# pic24OLED.net
KiCad netlist of a schematic drawn in EAGLE
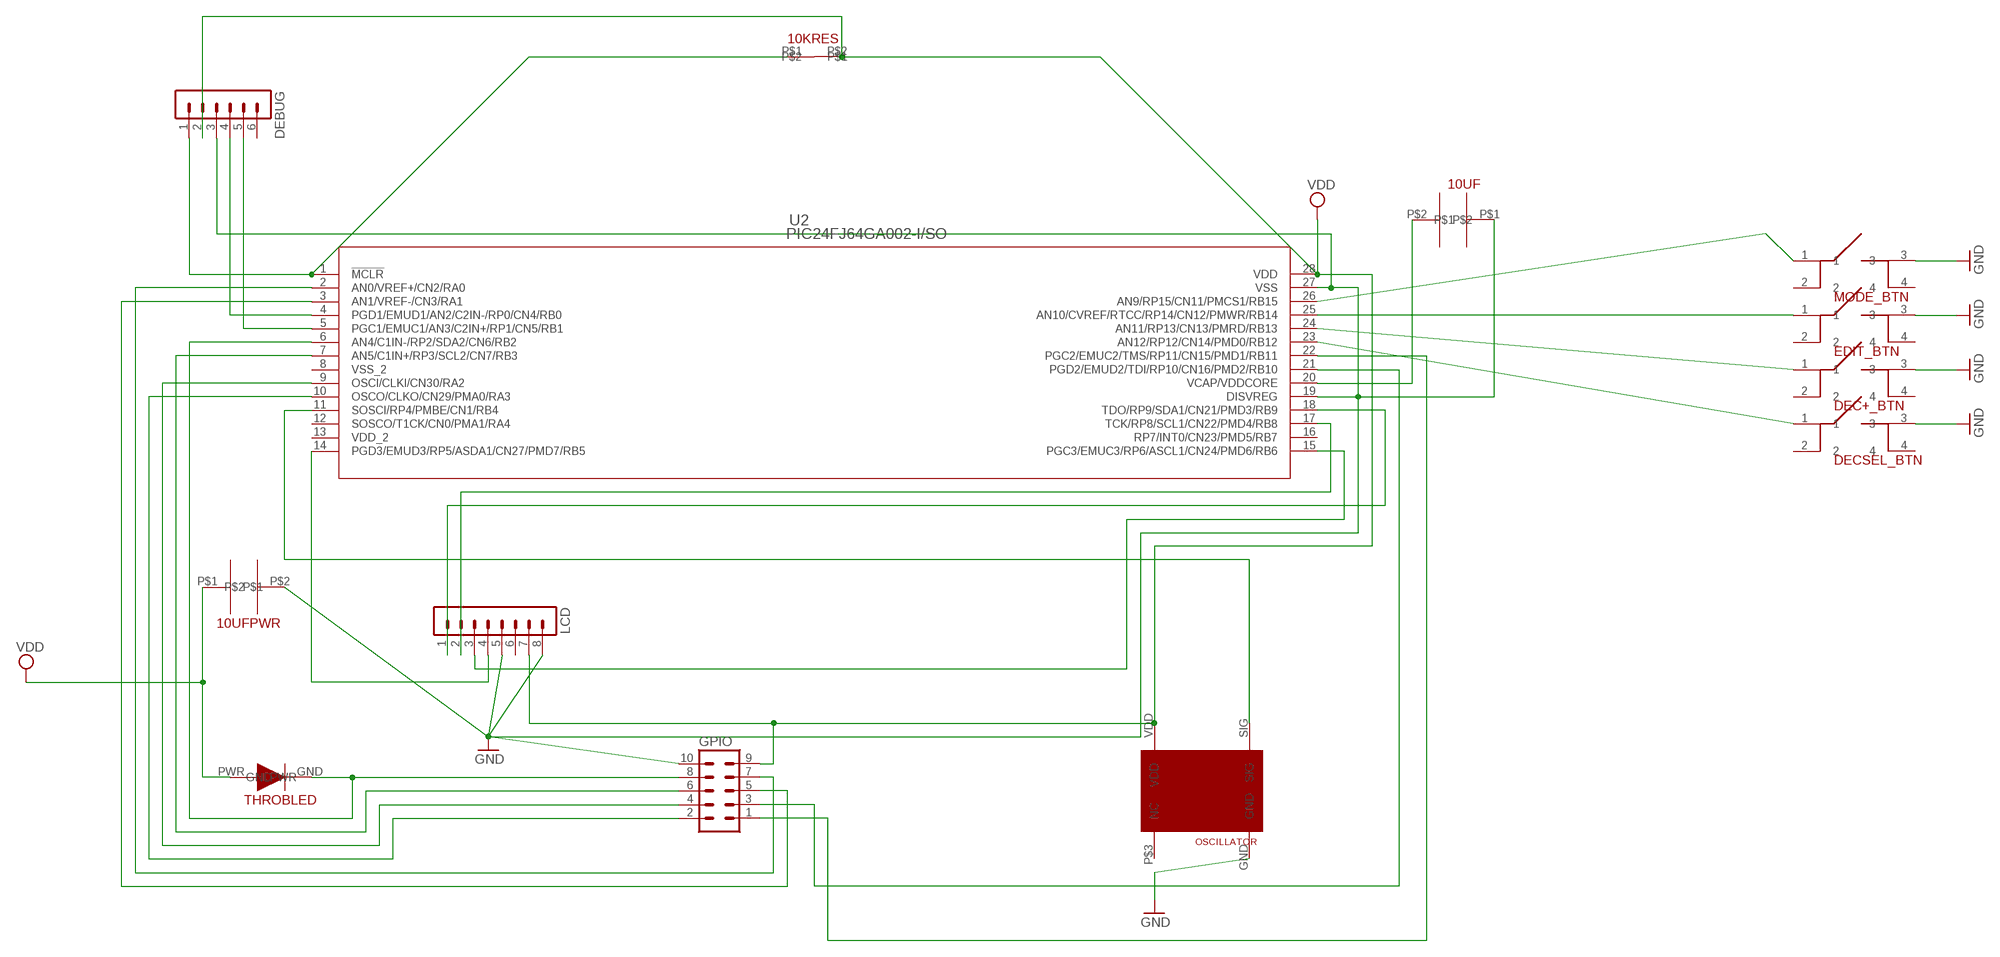
[diagram p0: schematic, sheet 1]

(export (version "E")
  (design (tool "Eeschema 10.0.6"))
  (components
    (comp (ref "10KRES")
      (value "THRESISTOR")
      (footprint "eagle-import:THRESISTOR")
      (libsource (lib "eagle-import") (part "THRESISTOR"))
    )
    (comp (ref "10UF")
      (value "THCAP")
      (footprint "eagle-import:THCAP")
      (libsource (lib "eagle-import") (part "THCAP"))
    )
    (comp (ref "10UFPWR")
      (value "THCAP")
      (footprint "eagle-import:THCAP")
      (libsource (lib "eagle-import") (part "THCAP"))
    )
    (comp (ref "DEBUG")
      (value "MA06-1")
      (footprint "eagle-import:MA06-1")
      (libsource (lib "eagle-import") (part "MA06-1"))
    )
    (comp (ref "DEC+_BTN")
      (value "PTS645-BUTTONPTS645")
      (footprint "eagle-import:TL3315-BUTTON")
      (libsource (lib "eagle-import") (part "PTS645-BUTTONPTS645"))
    )
    (comp (ref "DECSEL_BTN")
      (value "PTS645-BUTTONPTS645")
      (footprint "eagle-import:TL3315-BUTTON")
      (libsource (lib "eagle-import") (part "PTS645-BUTTONPTS645"))
    )
    (comp (ref "EDIT_BTN")
      (value "PTS645-BUTTONPTS645")
      (footprint "eagle-import:TL3315-BUTTON")
      (libsource (lib "eagle-import") (part "PTS645-BUTTONPTS645"))
    )
    (comp (ref "GPIO")
      (value "MA05-2")
      (footprint "eagle-import:MA05-2")
      (libsource (lib "eagle-import") (part "MA05-2"))
    )
    (comp (ref "LCD")
      (value "MA08-1")
      (footprint "eagle-import:MA08-1")
      (libsource (lib "eagle-import") (part "MA08-1"))
    )
    (comp (ref "MODE_BTN")
      (value "PTS645-BUTTONPTS645")
      (footprint "eagle-import:TL3315-BUTTON")
      (libsource (lib "eagle-import") (part "PTS645-BUTTONPTS645"))
    )
    (comp (ref "OSCILLATOR")
      (value "LX0-32.768OSCILLATOR")
      (footprint "eagle-import:LX0-32.768OSCILLATOR")
      (libsource (lib "eagle-import") (part "LX0-32.768OSCILLATOR"))
    )
    (comp (ref "THROBLED")
      (value "THLED")
      (footprint "eagle-import:THLED")
      (libsource (lib "eagle-import") (part "THLED"))
    )
    (comp (ref "U2")
      (value "PIC24FJ64GA002-I/SO")
      (footprint "eagle-import:SOIC28-W_MC")
      (fields (field (name "MANUFACTURER_PART_NUMBER") "PIC24FJ64GA002ISO"))
      (libsource (lib "eagle-import") (part "PIC24FJ64GA002-I/SO"))
    )
  )
  (nets
    (net (code "1") (name "GND") (class "Default")
      (node (ref "10UF") (pin "P$1") (pinfunction "P$1_P$1") (pintype "bidirectional"))
      (node (ref "10UFPWR") (pin "P$2") (pinfunction "P$2_P$2") (pintype "bidirectional"))
      (node (ref "DEBUG") (pin "3") (pinfunction "3_3") (pintype "passive"))
      (node (ref "DEC+_BTN") (pin "3") (pinfunction "3_3") (pintype "bidirectional"))
      (node (ref "DECSEL_BTN") (pin "3") (pinfunction "3_3") (pintype "bidirectional"))
      (node (ref "EDIT_BTN") (pin "3") (pinfunction "3_3") (pintype "bidirectional"))
      (node (ref "GPIO") (pin "10") (pinfunction "10_10") (pintype "passive"))
      (node (ref "LCD") (pin "5") (pinfunction "5_5") (pintype "passive"))
      (node (ref "LCD") (pin "8") (pinfunction "8_8") (pintype "passive"))
      (node (ref "MODE_BTN") (pin "3") (pinfunction "3_3") (pintype "bidirectional"))
      (node (ref "OSCILLATOR") (pin "GND") (pinfunction "GND_GND") (pintype "bidirectional"))
      (node (ref "U2") (pin "19") (pinfunction "DISVREG_19") (pintype "passive"))
      (node (ref "U2") (pin "27") (pinfunction "VSS_27") (pintype "passive"))
    )
    (net (code "2") (name "Net-(U2-AN0{slash}VREF+{slash}CN2{slash}RA0)") (class "Default")
      (node (ref "GPIO") (pin "7") (pinfunction "7_7") (pintype "passive"))
      (node (ref "U2") (pin "2") (pinfunction "AN0/VREF+/CN2/RA0_2") (pintype "passive"))
    )
    (net (code "3") (name "Net-(U2-AN1{slash}VREF-{slash}CN3{slash}RA1)") (class "Default")
      (node (ref "GPIO") (pin "5") (pinfunction "5_5") (pintype "passive"))
      (node (ref "U2") (pin "3") (pinfunction "AN1/VREF-/CN3/RA1_3") (pintype "passive"))
    )
    (net (code "4") (name "Net-(U2-AN4{slash}C1IN-{slash}RP2{slash}SDA2{slash}CN6{slash}RB2)") (class "Default")
      (node (ref "GPIO") (pin "8") (pinfunction "8_8") (pintype "passive"))
      (node (ref "THROBLED") (pin "GND") (pinfunction "GND_GND") (pintype "bidirectional"))
      (node (ref "U2") (pin "6") (pinfunction "AN4/C1IN-/RP2/SDA2/CN6/RB2_6") (pintype "passive"))
    )
    (net (code "5") (name "Net-(U2-AN5{slash}C1IN+{slash}RP3{slash}SCL2{slash}CN7{slash}RB3)") (class "Default")
      (node (ref "GPIO") (pin "6") (pinfunction "6_6") (pintype "passive"))
      (node (ref "U2") (pin "7") (pinfunction "AN5/C1IN+/RP3/SCL2/CN7/RB3_7") (pintype "passive"))
    )
    (net (code "6") (name "Net-(U2-AN9{slash}RP15{slash}CN11{slash}PMCS1{slash}RB15)") (class "Default")
      (node (ref "MODE_BTN") (pin "1") (pinfunction "1_1") (pintype "bidirectional"))
      (node (ref "U2") (pin "26") (pinfunction "AN9/RP15/CN11/PMCS1/RB15_26") (pintype "passive"))
    )
    (net (code "7") (name "Net-(U2-AN10{slash}CVREF{slash}RTCC{slash}RP14{slash}CN12{slash}PMWR{slash}RB14)") (class "Default")
      (node (ref "EDIT_BTN") (pin "1") (pinfunction "1_1") (pintype "bidirectional"))
      (node (ref "U2") (pin "25") (pinfunction "AN10/CVREF/RTCC/RP14/CN12/PMWR/RB14_25") (pintype "passive"))
    )
    (net (code "8") (name "Net-(U2-AN11{slash}RP13{slash}CN13{slash}PMRD{slash}RB13)") (class "Default")
      (node (ref "DEC+_BTN") (pin "1") (pinfunction "1_1") (pintype "bidirectional"))
      (node (ref "U2") (pin "24") (pinfunction "AN11/RP13/CN13/PMRD/RB13_24") (pintype "passive"))
    )
    (net (code "9") (name "Net-(U2-AN12{slash}RP12{slash}CN14{slash}PMD0{slash}RB12)") (class "Default")
      (node (ref "DECSEL_BTN") (pin "1") (pinfunction "1_1") (pintype "bidirectional"))
      (node (ref "U2") (pin "23") (pinfunction "AN12/RP12/CN14/PMD0/RB12_23") (pintype "passive"))
    )
    (net (code "10") (name "Net-(U2-OSCI{slash}CLKI{slash}CN30{slash}RA2)") (class "Default")
      (node (ref "GPIO") (pin "4") (pinfunction "4_4") (pintype "passive"))
      (node (ref "U2") (pin "9") (pinfunction "OSCI/CLKI/CN30/RA2_9") (pintype "passive"))
    )
    (net (code "11") (name "Net-(U2-OSCO{slash}CLKO{slash}CN29{slash}PMA0{slash}RA3)") (class "Default")
      (node (ref "GPIO") (pin "2") (pinfunction "2_2") (pintype "passive"))
      (node (ref "U2") (pin "10") (pinfunction "OSCO/CLKO/CN29/PMA0/RA3_10") (pintype "passive"))
    )
    (net (code "12") (name "Net-(U2-PGC1{slash}EMUC1{slash}AN3{slash}C2IN+{slash}RP1{slash}CN5{slash}RB1)") (class "Default")
      (node (ref "DEBUG") (pin "5") (pinfunction "5_5") (pintype "passive"))
      (node (ref "U2") (pin "5") (pinfunction "PGC1/EMUC1/AN3/C2IN+/RP1/CN5/RB1_5") (pintype "passive"))
    )
    (net (code "13") (name "Net-(U2-PGC2{slash}EMUC2{slash}TMS{slash}RP11{slash}CN15{slash}PMD1{slash}RB11)") (class "Default")
      (node (ref "GPIO") (pin "1") (pinfunction "1_1") (pintype "passive"))
      (node (ref "U2") (pin "22") (pinfunction "PGC2/EMUC2/TMS/RP11/CN15/PMD1/RB11_22") (pintype "passive"))
    )
    (net (code "14") (name "Net-(U2-PGC3{slash}EMUC3{slash}RP6{slash}ASCL1{slash}CN24{slash}PMD6{slash}RB6)") (class "Default")
      (node (ref "LCD") (pin "3") (pinfunction "3_3") (pintype "passive"))
      (node (ref "U2") (pin "15") (pinfunction "PGC3/EMUC3/RP6/ASCL1/CN24/PMD6/RB6_15") (pintype "passive"))
    )
    (net (code "15") (name "Net-(U2-PGD1{slash}EMUD1{slash}AN2{slash}C2IN-{slash}RP0{slash}CN4{slash}RB0)") (class "Default")
      (node (ref "DEBUG") (pin "4") (pinfunction "4_4") (pintype "passive"))
      (node (ref "U2") (pin "4") (pinfunction "PGD1/EMUD1/AN2/C2IN-/RP0/CN4/RB0_4") (pintype "passive"))
    )
    (net (code "16") (name "Net-(U2-PGD2{slash}EMUD2{slash}TDI{slash}RP10{slash}CN16{slash}PMD2{slash}RB10)") (class "Default")
      (node (ref "GPIO") (pin "3") (pinfunction "3_3") (pintype "passive"))
      (node (ref "U2") (pin "21") (pinfunction "PGD2/EMUD2/TDI/RP10/CN16/PMD2/RB10_21") (pintype "passive"))
    )
    (net (code "17") (name "Net-(U2-PGD3{slash}EMUD3{slash}RP5{slash}ASDA1{slash}CN27{slash}PMD7{slash}RB5)") (class "Default")
      (node (ref "LCD") (pin "4") (pinfunction "4_4") (pintype "passive"))
      (node (ref "U2") (pin "14") (pinfunction "PGD3/EMUD3/RP5/ASDA1/CN27/PMD7/RB5_14") (pintype "passive"))
    )
    (net (code "18") (name "Net-(U2-SOSCI{slash}RP4{slash}PMBE{slash}CN1{slash}RB4)") (class "Default")
      (node (ref "OSCILLATOR") (pin "SIG") (pinfunction "SIG_SIG") (pintype "bidirectional"))
      (node (ref "U2") (pin "11") (pinfunction "SOSCI/RP4/PMBE/CN1/RB4_11") (pintype "passive"))
    )
    (net (code "19") (name "Net-(U2-TCK{slash}RP8{slash}SCL1{slash}CN22{slash}PMD4{slash}RB8)") (class "Default")
      (node (ref "LCD") (pin "2") (pinfunction "2_2") (pintype "passive"))
      (node (ref "U2") (pin "17") (pinfunction "TCK/RP8/SCL1/CN22/PMD4/RB8_17") (pintype "passive"))
    )
    (net (code "20") (name "Net-(U2-TDO{slash}RP9{slash}SDA1{slash}CN21{slash}PMD3{slash}RB9)") (class "Default")
      (node (ref "LCD") (pin "1") (pinfunction "1_1") (pintype "passive"))
      (node (ref "U2") (pin "18") (pinfunction "TDO/RP9/SDA1/CN21/PMD3/RB9_18") (pintype "passive"))
    )
    (net (code "21") (name "Net-(U2-VCAP{slash}VDDCORE)") (class "Default")
      (node (ref "10UF") (pin "P$2") (pinfunction "P$2_P$2") (pintype "bidirectional"))
      (node (ref "U2") (pin "20") (pinfunction "VCAP/VDDCORE_20") (pintype "passive"))
    )
    (net (code "22") (name "Net-(U2-~{MCLR})") (class "Default")
      (node (ref "10KRES") (pin "P$1") (pinfunction "P$1_P$1") (pintype "bidirectional"))
      (node (ref "DEBUG") (pin "1") (pinfunction "1_1") (pintype "passive"))
      (node (ref "U2") (pin "1") (pinfunction "~{MCLR}_1") (pintype "passive"))
    )
    (net (code "23") (name "VDD") (class "Default")
      (node (ref "10KRES") (pin "P$2") (pinfunction "P$2_P$2") (pintype "bidirectional"))
      (node (ref "10UFPWR") (pin "P$1") (pinfunction "P$1_P$1") (pintype "bidirectional"))
      (node (ref "DEBUG") (pin "2") (pinfunction "2_2") (pintype "passive"))
      (node (ref "GPIO") (pin "9") (pinfunction "9_9") (pintype "passive"))
      (node (ref "LCD") (pin "7") (pinfunction "7_7") (pintype "passive"))
      (node (ref "OSCILLATOR") (pin "VDD") (pinfunction "VDD_VDD") (pintype "bidirectional"))
      (node (ref "THROBLED") (pin "PWR") (pinfunction "PWR_PWR") (pintype "bidirectional"))
      (node (ref "U2") (pin "28") (pinfunction "VDD_28") (pintype "passive"))
    )
    (net (code "24") (name "unconnected-(DEBUG-Pad6)") (class "Default")
      (node (ref "DEBUG") (pin "6") (pinfunction "6_6") (pintype "passive"))
    )
    (net (code "25") (name "unconnected-(DEC+_BTN-Pad2)") (class "Default")
      (node (ref "DEC+_BTN") (pin "2") (pinfunction "2_2") (pintype "bidirectional"))
    )
    (net (code "26") (name "unconnected-(DEC+_BTN-Pad4)") (class "Default")
      (node (ref "DEC+_BTN") (pin "4") (pinfunction "4_4") (pintype "bidirectional"))
    )
    (net (code "27") (name "unconnected-(DECSEL_BTN-Pad2)") (class "Default")
      (node (ref "DECSEL_BTN") (pin "2") (pinfunction "2_2") (pintype "bidirectional"))
    )
    (net (code "28") (name "unconnected-(DECSEL_BTN-Pad4)") (class "Default")
      (node (ref "DECSEL_BTN") (pin "4") (pinfunction "4_4") (pintype "bidirectional"))
    )
    (net (code "29") (name "unconnected-(EDIT_BTN-Pad2)") (class "Default")
      (node (ref "EDIT_BTN") (pin "2") (pinfunction "2_2") (pintype "bidirectional"))
    )
    (net (code "30") (name "unconnected-(EDIT_BTN-Pad4)") (class "Default")
      (node (ref "EDIT_BTN") (pin "4") (pinfunction "4_4") (pintype "bidirectional"))
    )
    (net (code "31") (name "unconnected-(LCD-Pad6)") (class "Default")
      (node (ref "LCD") (pin "6") (pinfunction "6_6") (pintype "passive"))
    )
    (net (code "32") (name "unconnected-(MODE_BTN-Pad2)") (class "Default")
      (node (ref "MODE_BTN") (pin "2") (pinfunction "2_2") (pintype "bidirectional"))
    )
    (net (code "33") (name "unconnected-(MODE_BTN-Pad4)") (class "Default")
      (node (ref "MODE_BTN") (pin "4") (pinfunction "4_4") (pintype "bidirectional"))
    )
    (net (code "34") (name "unconnected-(OSCILLATOR-NC-PadP$3)") (class "Default")
      (node (ref "OSCILLATOR") (pin "P$3") (pinfunction "NC_P$3") (pintype "bidirectional"))
    )
    (net (code "35") (name "unconnected-(U2-RP7{slash}INT0{slash}CN23{slash}PMD5{slash}RB7-Pad16)") (class "Default")
      (node (ref "U2") (pin "16") (pinfunction "RP7/INT0/CN23/PMD5/RB7_16") (pintype "passive"))
    )
    (net (code "36") (name "unconnected-(U2-SOSCO{slash}T1CK{slash}CN0{slash}PMA1{slash}RA4-Pad12)") (class "Default")
      (node (ref "U2") (pin "12") (pinfunction "SOSCO/T1CK/CN0/PMA1/RA4_12") (pintype "passive"))
    )
    (net (code "37") (name "unconnected-(U2-VDD_2-Pad13)") (class "Default")
      (node (ref "U2") (pin "13") (pinfunction "VDD_2_13") (pintype "passive"))
    )
    (net (code "38") (name "unconnected-(U2-VSS_2-Pad8)") (class "Default")
      (node (ref "U2") (pin "8") (pinfunction "VSS_2_8") (pintype "passive"))
    )
  )
)
